# ST-Link-V2_2.net
KiCad netlist of a schematic drawn in Altium Designer
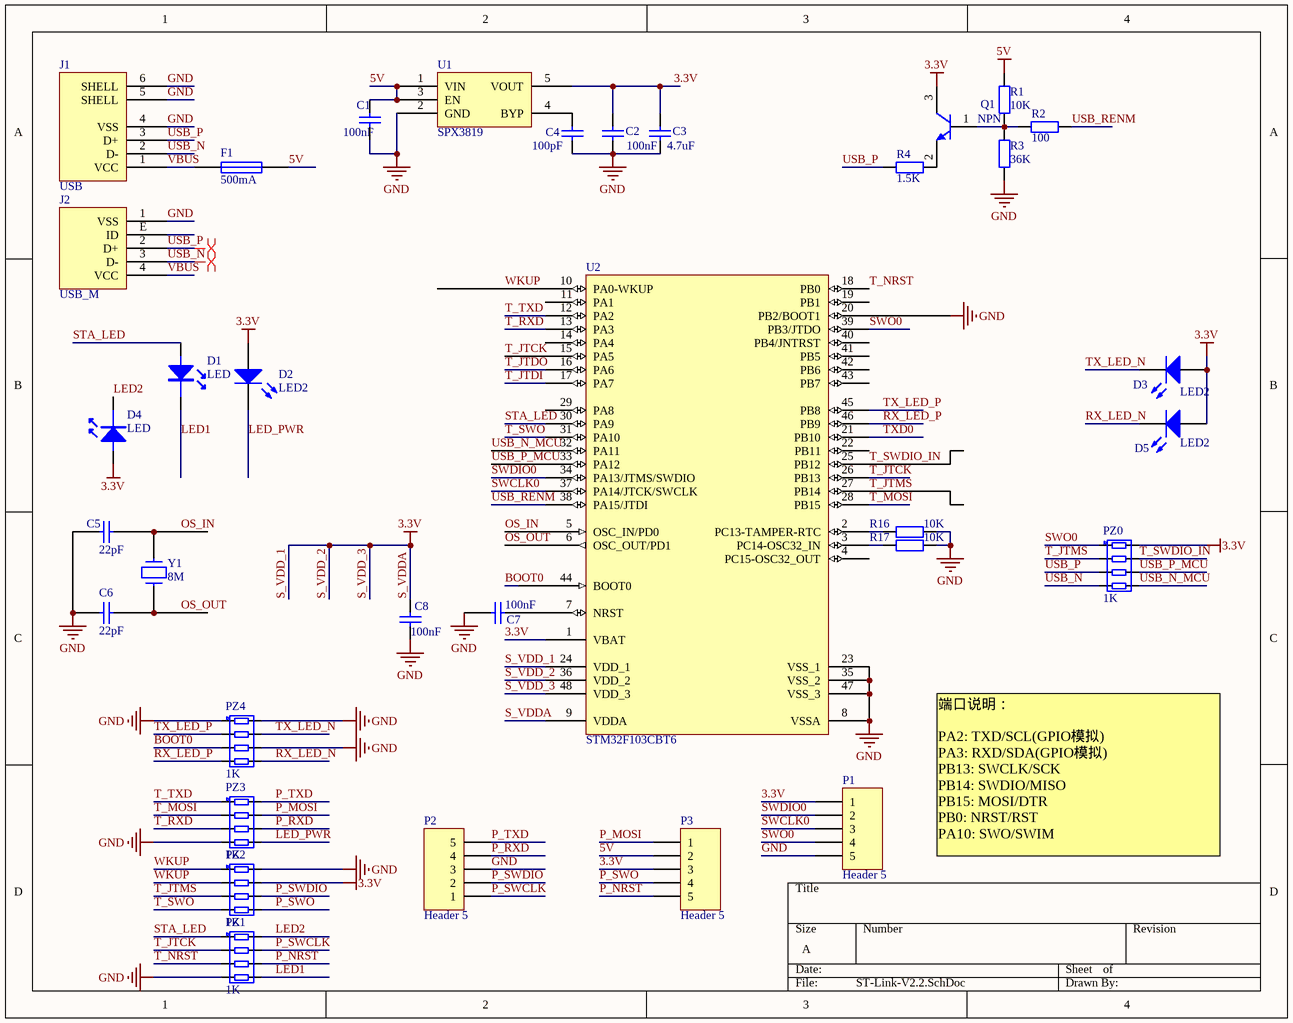
[diagram p0: ST-Link-V2.2.SchDoc]

(export (version "E")
  (design (tool "Eeschema 10.0.6"))
  (components
    (comp (ref "C1")
      (value "100nF")
      (footprint "C-0603")
      (description "Capacitor")
      (fields (field (name "Comment") "Cap") (field (name "PUBLISHER") "Altium Limited"))
      (libsource (lib "Miscellaneous Devices") (part "Cap"))
    )
    (comp (ref "C2")
      (value "100nF")
      (footprint "C-0603")
      (description "Capacitor")
      (fields (field (name "Comment") "Cap") (field (name "PUBLISHER") "Altium Limited"))
      (libsource (lib "Miscellaneous Devices") (part "Cap"))
    )
    (comp (ref "C3")
      (value "4.7uF")
      (footprint "C-0603")
      (description "Capacitor")
      (fields (field (name "Comment") "Cap") (field (name "PUBLISHER") "Altium Limited"))
      (libsource (lib "Miscellaneous Devices") (part "Cap"))
    )
    (comp (ref "C4")
      (value "100pF")
      (footprint "C-0603")
      (description "Capacitor")
      (fields (field (name "Comment") "Cap") (field (name "PUBLISHER") "Altium Limited"))
      (libsource (lib "Miscellaneous Devices") (part "Cap"))
    )
    (comp (ref "C5")
      (value "22pF")
      (footprint "C-0603")
      (fields (field (name "Comment") "Cap"))
      (libsource (lib "WK_PCB") (part "Cap"))
    )
    (comp (ref "C6")
      (value "22pF")
      (footprint "C-0603")
      (fields (field (name "Comment") "Cap"))
      (libsource (lib "WK_PCB") (part "Cap"))
    )
    (comp (ref "C7")
      (value "100nF")
      (footprint "C-0603")
      (fields (field (name "Comment") "Cap"))
      (libsource (lib "WK_PCB") (part "Cap"))
    )
    (comp (ref "C8")
      (value "100nF")
      (footprint "C-0603")
      (description "Capacitor")
      (fields (field (name "Comment") "Cap") (field (name "PUBLISHER") "Altium Limited"))
      (libsource (lib "Miscellaneous Devices") (part "Cap"))
    )
    (comp (ref "D1")
      (value "LED")
      (footprint "SMT_LED_0603")
      (description "LED 发光二极管")
      (libsource (lib "WK_PCB") (part "LED"))
    )
    (comp (ref "D2")
      (value "LED2")
      (footprint "SMT_LED_0603")
      (description "Typical RED, GREEN, YELLOW, AMBER GaAs LED")
      (fields (field (name "PUBLISHER") "Altium Limited"))
      (libsource (lib "Miscellaneous Devices") (part "LED2"))
    )
    (comp (ref "D3")
      (value "LED2")
      (footprint "SMT_LED_0603")
      (description "Typical RED, GREEN, YELLOW, AMBER GaAs LED")
      (fields (field (name "PUBLISHER") "Altium Limited"))
      (libsource (lib "Miscellaneous Devices") (part "LED2"))
    )
    (comp (ref "D4")
      (value "LED")
      (footprint "SMT_LED_0603")
      (description "LED 发光二极管")
      (libsource (lib "WK_PCB") (part "LED"))
    )
    (comp (ref "D5")
      (value "LED2")
      (footprint "SMT_LED_0603")
      (description "Typical RED, GREEN, YELLOW, AMBER GaAs LED")
      (fields (field (name "PUBLISHER") "Altium Limited"))
      (libsource (lib "Miscellaneous Devices") (part "LED2"))
    )
    (comp (ref "F1")
      (value "500mA")
      (footprint "0805-1")
      (description "保险丝")
      (fields (field (name "Comment") "Fuse1"))
      (libsource (lib "Fszhang") (part "Fuse1"))
    )
    (comp (ref "J1")
      (value "USB")
      (footprint "USB-B")
      (description "USB接口")
      (libsource (lib "HDR_Fszhang") (part "USB"))
    )
    (comp (ref "J2")
      (value "USB_M")
      (footprint "USB_MICRO_5S_B")
      (description "Micro/Mini USB")
      (libsource (lib "HDR_Fszhang") (part "USB_M"))
    )
    (comp (ref "P1")
      (value "Header 5")
      (footprint "SIP5-1.27")
      (description "Header, 5-Pin")
      (fields (field (name "PUBLISHER") "Altium Limited"))
      (libsource (lib "Miscellaneous Connectors") (part "Header 5"))
    )
    (comp (ref "P2")
      (value "Header 5")
      (footprint "HEADER 5")
      (description "Header, 5-Pin")
      (fields (field (name "PUBLISHER") "Altium Limited"))
      (libsource (lib "") (part "Header 5_1"))
    )
    (comp (ref "P3")
      (value "Header 5")
      (footprint "HEADER 5")
      (description "Header, 5-Pin")
      (fields (field (name "PUBLISHER") "Altium Limited"))
      (libsource (lib "Miscellaneous Connectors") (part "Header 5"))
    )
    (comp (ref "PZ0") (value "1K") (footprint "AR0603*4") (libsource (lib "R_ARRAY_SCHLIB") (part "RES4R")))
    (comp (ref "PZ1") (value "1K") (footprint "AR0603*4") (libsource (lib "R_ARRAY_SCHLIB") (part "RES4R")))
    (comp (ref "PZ2") (value "1K") (footprint "AR0603*4") (libsource (lib "R_ARRAY_SCHLIB") (part "RES4R")))
    (comp (ref "PZ3") (value "1K") (footprint "AR0603*4") (libsource (lib "R_ARRAY_SCHLIB") (part "RES4R")))
    (comp (ref "PZ4") (value "1K") (footprint "AR0603*4") (libsource (lib "R_ARRAY_SCHLIB") (part "RES4R")))
    (comp (ref "Q1")
      (value "NPN")
      (footprint "SOT23-3")
      (description "贴片三极管")
      (fields (field (name "PUBLISHER") "Altium Limited"))
      (libsource (lib "Fszhang") (part "NPN1"))
    )
    (comp (ref "R1")
      (value "10K")
      (footprint "0603-1")
      (description "贴片电阻")
      (fields (field (name "Comment") "Res1") (field (name "PUBLISHER") "Altium Limited"))
      (libsource (lib "") (part "Res1_2"))
    )
    (comp (ref "R2")
      (value "100")
      (footprint "0603-1")
      (description "贴片电阻")
      (fields (field (name "Comment") "Res1") (field (name "PUBLISHER") "Altium Limited"))
      (libsource (lib "") (part "Res1_1"))
    )
    (comp (ref "R3")
      (value "36K")
      (footprint "0603-1")
      (description "贴片电阻")
      (fields (field (name "Comment") "Res1") (field (name "PUBLISHER") "Altium Limited"))
      (libsource (lib "") (part "Res1_2"))
    )
    (comp (ref "R4")
      (value "1.5K")
      (footprint "0603-1")
      (description "贴片电阻")
      (fields (field (name "Comment") "Res1") (field (name "PUBLISHER") "Altium Limited"))
      (libsource (lib "Fszhang") (part "Res1"))
    )
    (comp (ref "R16")
      (value "10K")
      (footprint "0603-1")
      (description "贴片电阻")
      (fields (field (name "Comment") "Res1") (field (name "PUBLISHER") "Altium Limited"))
      (libsource (lib "") (part "Res1_1"))
    )
    (comp (ref "R17")
      (value "10K")
      (footprint "0603-1")
      (description "贴片电阻")
      (fields (field (name "Comment") "Res1") (field (name "PUBLISHER") "Altium Limited"))
      (libsource (lib "") (part "Res1_1"))
    )
    (comp (ref "U1") (value "SPX3819") (footprint "SOT23-5") (libsource (lib "Schlib1") (part "SPX3819")))
    (comp (ref "U2")
      (value "STM32F103CBT6")
      (footprint "LQFP48_N")
      (description "STM32 ARM-based 32-bit MCU with 64 Kbytes Flash, 48-pin LQFP, Industrial Temperature")
      (fields (field (name "PUBLISHER") "Altium Limited"))
      (libsource (lib "ST Microcontroller 32-Bit STM32") (part "STM32F103C8T6"))
    )
    (comp (ref "Y1") (value "8M") (footprint "XAL5032 2-Leads") (libsource (lib "WK_PCB") (part "XTAL")))
  )
  (nets
    (net (code "1") (name "/BOOT0") (class "Default")
      (node (ref "PZ4") (pin "3") (pintype "passive"))
      (node (ref "U2") (pin "44") (pinfunction "BOOT0_44") (pintype "input"))
    )
    (net (code "2") (name "/LED1") (class "Default")
      (node (ref "D1") (pin "2") (pinfunction "K_2") (pintype "passive"))
      (node (ref "PZ1") (pin "5") (pintype "passive"))
    )
    (net (code "3") (name "/LED2") (class "Default")
      (node (ref "D4") (pin "2") (pinfunction "K_2") (pintype "passive"))
      (node (ref "PZ1") (pin "8") (pintype "passive"))
    )
    (net (code "4") (name "/LED_PWR") (class "Default")
      (node (ref "D2") (pin "2") (pinfunction "K_2") (pintype "passive"))
      (node (ref "PZ3") (pin "5") (pintype "passive"))
    )
    (net (code "5") (name "/OS_IN") (class "Default")
      (node (ref "C5") (pin "2") (pinfunction "2_2") (pintype "passive"))
      (node (ref "U2") (pin "5") (pinfunction "OSC_IN/PD0_5") (pintype "input"))
      (node (ref "Y1") (pin "2") (pinfunction "2_2") (pintype "passive"))
    )
    (net (code "6") (name "/OS_OUT") (class "Default")
      (node (ref "C6") (pin "2") (pinfunction "2_2") (pintype "passive"))
      (node (ref "U2") (pin "6") (pinfunction "OSC_OUT/PD1_6") (pintype "output"))
      (node (ref "Y1") (pin "1") (pinfunction "1_1") (pintype "passive"))
    )
    (net (code "7") (name "/P_MOSI") (class "Default")
      (node (ref "P3") (pin "1") (pinfunction "1_1") (pintype "passive"))
      (node (ref "PZ3") (pin "7") (pintype "passive"))
    )
    (net (code "8") (name "/P_NRST") (class "Default")
      (node (ref "P3") (pin "5") (pinfunction "5_5") (pintype "passive"))
      (node (ref "PZ1") (pin "6") (pintype "passive"))
    )
    (net (code "9") (name "/P_RXD") (class "Default")
      (node (ref "P2") (pin "4") (pinfunction "4_4") (pintype "passive"))
      (node (ref "PZ3") (pin "6") (pintype "passive"))
    )
    (net (code "10") (name "/P_SWCLK") (class "Default")
      (node (ref "P2") (pin "1") (pinfunction "1_1") (pintype "passive"))
      (node (ref "PZ1") (pin "7") (pintype "passive"))
    )
    (net (code "11") (name "/P_SWDIO") (class "Default")
      (node (ref "P2") (pin "2") (pinfunction "2_2") (pintype "passive"))
      (node (ref "PZ2") (pin "6") (pintype "passive"))
    )
    (net (code "12") (name "/P_SWO") (class "Default")
      (node (ref "P3") (pin "4") (pinfunction "4_4") (pintype "passive"))
      (node (ref "PZ2") (pin "5") (pintype "passive"))
    )
    (net (code "13") (name "/P_TXD") (class "Default")
      (node (ref "P2") (pin "5") (pinfunction "5_5") (pintype "passive"))
      (node (ref "PZ3") (pin "8") (pintype "passive"))
    )
    (net (code "14") (name "/RX_LED_N") (class "Default")
      (node (ref "D5") (pin "2") (pinfunction "K_2") (pintype "passive"))
      (node (ref "PZ4") (pin "5") (pintype "passive"))
    )
    (net (code "15") (name "/RX_LED_P") (class "Default")
      (node (ref "PZ4") (pin "4") (pintype "passive"))
      (node (ref "U2") (pin "46") (pinfunction "PB9_46") (pintype "bidirectional"))
    )
    (net (code "16") (name "/STA_LED") (class "Default")
      (node (ref "D1") (pin "1") (pinfunction "A_1") (pintype "passive"))
      (node (ref "PZ1") (pin "1") (pintype "passive"))
      (node (ref "U2") (pin "30") (pinfunction "PA9_30") (pintype "bidirectional"))
    )
    (net (code "17") (name "/SWCLK0") (class "Default")
      (node (ref "P1") (pin "3") (pinfunction "3_3") (pintype "passive"))
      (node (ref "U2") (pin "37") (pinfunction "PA14/JTCK/SWCLK_37") (pintype "bidirectional"))
    )
    (net (code "18") (name "/SWDIO0") (class "Default")
      (node (ref "P1") (pin "2") (pinfunction "2_2") (pintype "passive"))
      (node (ref "U2") (pin "34") (pinfunction "PA13/JTMS/SWDIO_34") (pintype "bidirectional"))
    )
    (net (code "19") (name "/SWO0") (class "Default")
      (node (ref "P1") (pin "4") (pinfunction "4_4") (pintype "passive"))
      (node (ref "PZ0") (pin "1") (pintype "passive"))
      (node (ref "U2") (pin "39") (pinfunction "PB3/JTDO_39") (pintype "bidirectional"))
    )
    (net (code "20") (name "/TXD0") (class "Default")
      (node (ref "U2") (pin "21") (pinfunction "PB10_21") (pintype "bidirectional"))
    )
    (net (code "21") (name "/TX_LED_N") (class "Default")
      (node (ref "D3") (pin "2") (pinfunction "K_2") (pintype "passive"))
      (node (ref "PZ4") (pin "7") (pintype "passive"))
    )
    (net (code "22") (name "/TX_LED_P") (class "Default")
      (node (ref "PZ4") (pin "2") (pintype "passive"))
      (node (ref "U2") (pin "45") (pinfunction "PB8_45") (pintype "bidirectional"))
    )
    (net (code "23") (name "/T_JTCK") (class "Default")
      (node (ref "PZ1") (pin "2") (pintype "passive"))
      (node (ref "U2") (pin "15") (pinfunction "PA5_15") (pintype "bidirectional"))
      (node (ref "U2") (pin "26") (pinfunction "PB13_26") (pintype "bidirectional"))
    )
    (net (code "24") (name "/T_JTDI") (class "Default")
      (node (ref "U2") (pin "17") (pinfunction "PA7_17") (pintype "bidirectional"))
    )
    (net (code "25") (name "/T_JTDO") (class "Default")
      (node (ref "U2") (pin "16") (pinfunction "PA6_16") (pintype "bidirectional"))
    )
    (net (code "26") (name "/T_JTMS") (class "Default")
      (node (ref "PZ0") (pin "2") (pintype "passive"))
      (node (ref "PZ2") (pin "3") (pintype "passive"))
      (node (ref "U2") (pin "27") (pinfunction "PB14_27") (pintype "bidirectional"))
    )
    (net (code "27") (name "/T_MOSI") (class "Default")
      (node (ref "PZ3") (pin "2") (pintype "passive"))
      (node (ref "U2") (pin "28") (pinfunction "PB15_28") (pintype "bidirectional"))
    )
    (net (code "28") (name "/T_NRST") (class "Default")
      (node (ref "PZ1") (pin "3") (pintype "passive"))
      (node (ref "U2") (pin "18") (pinfunction "PB0_18") (pintype "bidirectional"))
    )
    (net (code "29") (name "/T_RXD") (class "Default")
      (node (ref "PZ3") (pin "3") (pintype "passive"))
      (node (ref "U2") (pin "13") (pinfunction "PA3_13") (pintype "bidirectional"))
    )
    (net (code "30") (name "/T_SWDIO_IN") (class "Default")
      (node (ref "PZ0") (pin "7") (pintype "passive"))
      (node (ref "U2") (pin "25") (pinfunction "PB12_25") (pintype "bidirectional"))
    )
    (net (code "31") (name "/T_SWO") (class "Default")
      (node (ref "PZ2") (pin "4") (pintype "passive"))
      (node (ref "U2") (pin "31") (pinfunction "PA10_31") (pintype "bidirectional"))
    )
    (net (code "32") (name "/T_TXD") (class "Default")
      (node (ref "PZ3") (pin "1") (pintype "passive"))
      (node (ref "U2") (pin "12") (pinfunction "PA2_12") (pintype "bidirectional"))
    )
    (net (code "33") (name "/USB_N") (class "Default")
      (node (ref "J1") (pin "2") (pinfunction "D-_2") (pintype "passive"))
      (node (ref "J2") (pin "3") (pinfunction "D-_3") (pintype "passive"))
      (node (ref "PZ0") (pin "4") (pintype "passive"))
    )
    (net (code "34") (name "/USB_N_MCU") (class "Default")
      (node (ref "PZ0") (pin "5") (pintype "passive"))
      (node (ref "U2") (pin "32") (pinfunction "PA11_32") (pintype "bidirectional"))
    )
    (net (code "35") (name "/USB_P") (class "Default")
      (node (ref "J1") (pin "3") (pinfunction "D+_3") (pintype "passive"))
      (node (ref "J2") (pin "2") (pinfunction "D+_2") (pintype "passive"))
      (node (ref "PZ0") (pin "3") (pintype "passive"))
      (node (ref "R4") (pin "2") (pinfunction "2_2") (pintype "passive"))
    )
    (net (code "36") (name "/USB_P_MCU") (class "Default")
      (node (ref "PZ0") (pin "6") (pintype "passive"))
      (node (ref "U2") (pin "33") (pinfunction "PA12_33") (pintype "bidirectional"))
    )
    (net (code "37") (name "/USB_RENM") (class "Default")
      (node (ref "R2") (pin "2") (pinfunction "2_2") (pintype "passive"))
      (node (ref "U2") (pin "38") (pinfunction "PA15/JTDI_38") (pintype "bidirectional"))
    )
    (net (code "38") (name "/VBUS") (class "Default")
      (node (ref "F1") (pin "2") (pinfunction "2_2") (pintype "passive"))
      (node (ref "J1") (pin "1") (pinfunction "VCC_1") (pintype "passive"))
      (node (ref "J2") (pin "4") (pinfunction "VCC_4") (pintype "passive"))
    )
    (net (code "39") (name "/WKUP") (class "Default")
      (node (ref "PZ2") (pin "1") (pintype "passive"))
      (node (ref "PZ2") (pin "2") (pintype "passive"))
      (node (ref "U2") (pin "10") (pinfunction "PA0-WKUP_10") (pintype "bidirectional"))
    )
    (net (code "40") (name "3.3V") (class "Default")
      (node (ref "C2") (pin "2") (pinfunction "2_2") (pintype "passive"))
      (node (ref "C3") (pin "2") (pinfunction "2_2") (pintype "passive"))
      (node (ref "C8") (pin "2") (pinfunction "2_2") (pintype "passive"))
      (node (ref "D2") (pin "1") (pinfunction "A_1") (pintype "passive"))
      (node (ref "D3") (pin "1") (pinfunction "A_1") (pintype "passive"))
      (node (ref "D4") (pin "1") (pinfunction "A_1") (pintype "passive"))
      (node (ref "D5") (pin "1") (pinfunction "A_1") (pintype "passive"))
      (node (ref "P1") (pin "1") (pinfunction "1_1") (pintype "passive"))
      (node (ref "P3") (pin "3") (pinfunction "3_3") (pintype "passive"))
      (node (ref "PZ0") (pin "8") (pintype "passive"))
      (node (ref "PZ2") (pin "7") (pintype "passive"))
      (node (ref "Q1") (pin "3") (pinfunction "C_3") (pintype "passive"))
      (node (ref "U1") (pin "5") (pinfunction "VOUT_5") (pintype "passive"))
      (node (ref "U2") (pin "1") (pinfunction "VBAT_1") (pintype "power_in"))
      (node (ref "U2") (pin "24") (pinfunction "VDD_1_24") (pintype "power_in"))
      (node (ref "U2") (pin "36") (pinfunction "VDD_2_36") (pintype "power_in"))
      (node (ref "U2") (pin "48") (pinfunction "VDD_3_48") (pintype "power_in"))
      (node (ref "U2") (pin "9") (pinfunction "VDDA_9") (pintype "power_in"))
    )
    (net (code "41") (name "5V") (class "Default")
      (node (ref "C1") (pin "2") (pinfunction "2_2") (pintype "passive"))
      (node (ref "F1") (pin "1") (pinfunction "1_1") (pintype "passive"))
      (node (ref "P3") (pin "2") (pinfunction "2_2") (pintype "passive"))
      (node (ref "R1") (pin "1") (pinfunction "1_1") (pintype "passive"))
      (node (ref "U1") (pin "1") (pinfunction "VIN_1") (pintype "passive"))
      (node (ref "U1") (pin "3") (pinfunction "EN_3") (pintype "passive"))
    )
    (net (code "42") (name "GND") (class "Default")
      (node (ref "C1") (pin "1") (pinfunction "1_1") (pintype "passive"))
      (node (ref "C2") (pin "1") (pinfunction "1_1") (pintype "passive"))
      (node (ref "C3") (pin "1") (pinfunction "1_1") (pintype "passive"))
      (node (ref "C4") (pin "1") (pinfunction "1_1") (pintype "passive"))
      (node (ref "C5") (pin "1") (pinfunction "1_1") (pintype "passive"))
      (node (ref "C6") (pin "1") (pinfunction "1_1") (pintype "passive"))
      (node (ref "C7") (pin "1") (pinfunction "1_1") (pintype "passive"))
      (node (ref "C8") (pin "1") (pinfunction "1_1") (pintype "passive"))
      (node (ref "J1") (pin "4") (pinfunction "VSS_4") (pintype "passive"))
      (node (ref "J1") (pin "5") (pinfunction "SHELL_5") (pintype "passive"))
      (node (ref "J1") (pin "6") (pinfunction "SHELL_6") (pintype "passive"))
      (node (ref "J2") (pin "1") (pinfunction "VSS_1") (pintype "passive"))
      (node (ref "P1") (pin "5") (pinfunction "5_5") (pintype "passive"))
      (node (ref "P2") (pin "3") (pinfunction "3_3") (pintype "passive"))
      (node (ref "PZ1") (pin "4") (pintype "passive"))
      (node (ref "PZ2") (pin "8") (pintype "passive"))
      (node (ref "PZ3") (pin "4") (pintype "passive"))
      (node (ref "PZ4") (pin "1") (pintype "passive"))
      (node (ref "PZ4") (pin "6") (pintype "passive"))
      (node (ref "PZ4") (pin "8") (pintype "passive"))
      (node (ref "R16") (pin "2") (pinfunction "2_2") (pintype "passive"))
      (node (ref "R17") (pin "2") (pinfunction "2_2") (pintype "passive"))
      (node (ref "R3") (pin "2") (pinfunction "2_2") (pintype "passive"))
      (node (ref "U1") (pin "2") (pinfunction "GND_2") (pintype "passive"))
      (node (ref "U2") (pin "20") (pinfunction "PB2/BOOT1_20") (pintype "bidirectional"))
      (node (ref "U2") (pin "23") (pinfunction "VSS_1_23") (pintype "power_in"))
      (node (ref "U2") (pin "35") (pinfunction "VSS_2_35") (pintype "power_in"))
      (node (ref "U2") (pin "47") (pinfunction "VSS_3_47") (pintype "power_in"))
      (node (ref "U2") (pin "8") (pinfunction "VSSA_8") (pintype "power_in"))
    )
    (net (code "43") (name "Net-(Q1-B)") (class "Default")
      (node (ref "Q1") (pin "1") (pinfunction "B_1") (pintype "passive"))
      (node (ref "R1") (pin "2") (pinfunction "2_2") (pintype "passive"))
      (node (ref "R2") (pin "1") (pinfunction "1_1") (pintype "passive"))
      (node (ref "R3") (pin "1") (pinfunction "1_1") (pintype "passive"))
    )
    (net (code "44") (name "Net-(Q1-E)") (class "Default")
      (node (ref "Q1") (pin "2") (pinfunction "E_2") (pintype "passive"))
      (node (ref "R4") (pin "1") (pinfunction "1_1") (pintype "passive"))
    )
    (net (code "45") (name "Net-(U1-BYP)") (class "Default")
      (node (ref "C4") (pin "2") (pinfunction "2_2") (pintype "passive"))
      (node (ref "U1") (pin "4") (pinfunction "BYP_4") (pintype "passive"))
    )
    (net (code "46") (name "Net-(U2-NRST)") (class "Default")
      (node (ref "C7") (pin "2") (pinfunction "2_2") (pintype "passive"))
      (node (ref "U2") (pin "7") (pinfunction "NRST_7") (pintype "bidirectional"))
    )
    (net (code "47") (name "Net-(U2-PC13-TAMPER-RTC)") (class "Default")
      (node (ref "R16") (pin "1") (pinfunction "1_1") (pintype "passive"))
      (node (ref "U2") (pin "2") (pinfunction "PC13-TAMPER-RTC_2") (pintype "bidirectional"))
    )
    (net (code "48") (name "Net-(U2-PC14-OSC32_IN)") (class "Default")
      (node (ref "R17") (pin "1") (pinfunction "1_1") (pintype "passive"))
      (node (ref "U2") (pin "3") (pinfunction "PC14-OSC32_IN_3") (pintype "bidirectional"))
    )
    (net (code "49") (name "unconnected-(J2-ID-PadE)") (class "Default")
      (node (ref "J2") (pin "E") (pinfunction "ID_E") (pintype "passive"))
    )
    (net (code "50") (name "unconnected-(U2-PA1-Pad11)") (class "Default")
      (node (ref "U2") (pin "11") (pinfunction "PA1_11") (pintype "bidirectional"))
    )
    (net (code "51") (name "unconnected-(U2-PA4-Pad14)") (class "Default")
      (node (ref "U2") (pin "14") (pinfunction "PA4_14") (pintype "bidirectional"))
    )
    (net (code "52") (name "unconnected-(U2-PA8-Pad29)") (class "Default")
      (node (ref "U2") (pin "29") (pinfunction "PA8_29") (pintype "bidirectional"))
    )
    (net (code "53") (name "unconnected-(U2-PB1-Pad19)") (class "Default")
      (node (ref "U2") (pin "19") (pinfunction "PB1_19") (pintype "bidirectional"))
    )
    (net (code "54") (name "unconnected-(U2-PB4{slash}JNTRST-Pad40)") (class "Default")
      (node (ref "U2") (pin "40") (pinfunction "PB4/JNTRST_40") (pintype "bidirectional"))
    )
    (net (code "55") (name "unconnected-(U2-PB5-Pad41)") (class "Default")
      (node (ref "U2") (pin "41") (pinfunction "PB5_41") (pintype "bidirectional"))
    )
    (net (code "56") (name "unconnected-(U2-PB6-Pad42)") (class "Default")
      (node (ref "U2") (pin "42") (pinfunction "PB6_42") (pintype "bidirectional"))
    )
    (net (code "57") (name "unconnected-(U2-PB7-Pad43)") (class "Default")
      (node (ref "U2") (pin "43") (pinfunction "PB7_43") (pintype "bidirectional"))
    )
    (net (code "58") (name "unconnected-(U2-PB11-Pad22)") (class "Default")
      (node (ref "U2") (pin "22") (pinfunction "PB11_22") (pintype "bidirectional"))
    )
    (net (code "59") (name "unconnected-(U2-PC15-OSC32_OUT-Pad4)") (class "Default")
      (node (ref "U2") (pin "4") (pinfunction "PC15-OSC32_OUT_4") (pintype "bidirectional"))
    )
  )
)
